# IEEE_EXT_Base_Centr.net
KiCad netlist of a schematic drawn in EAGLE
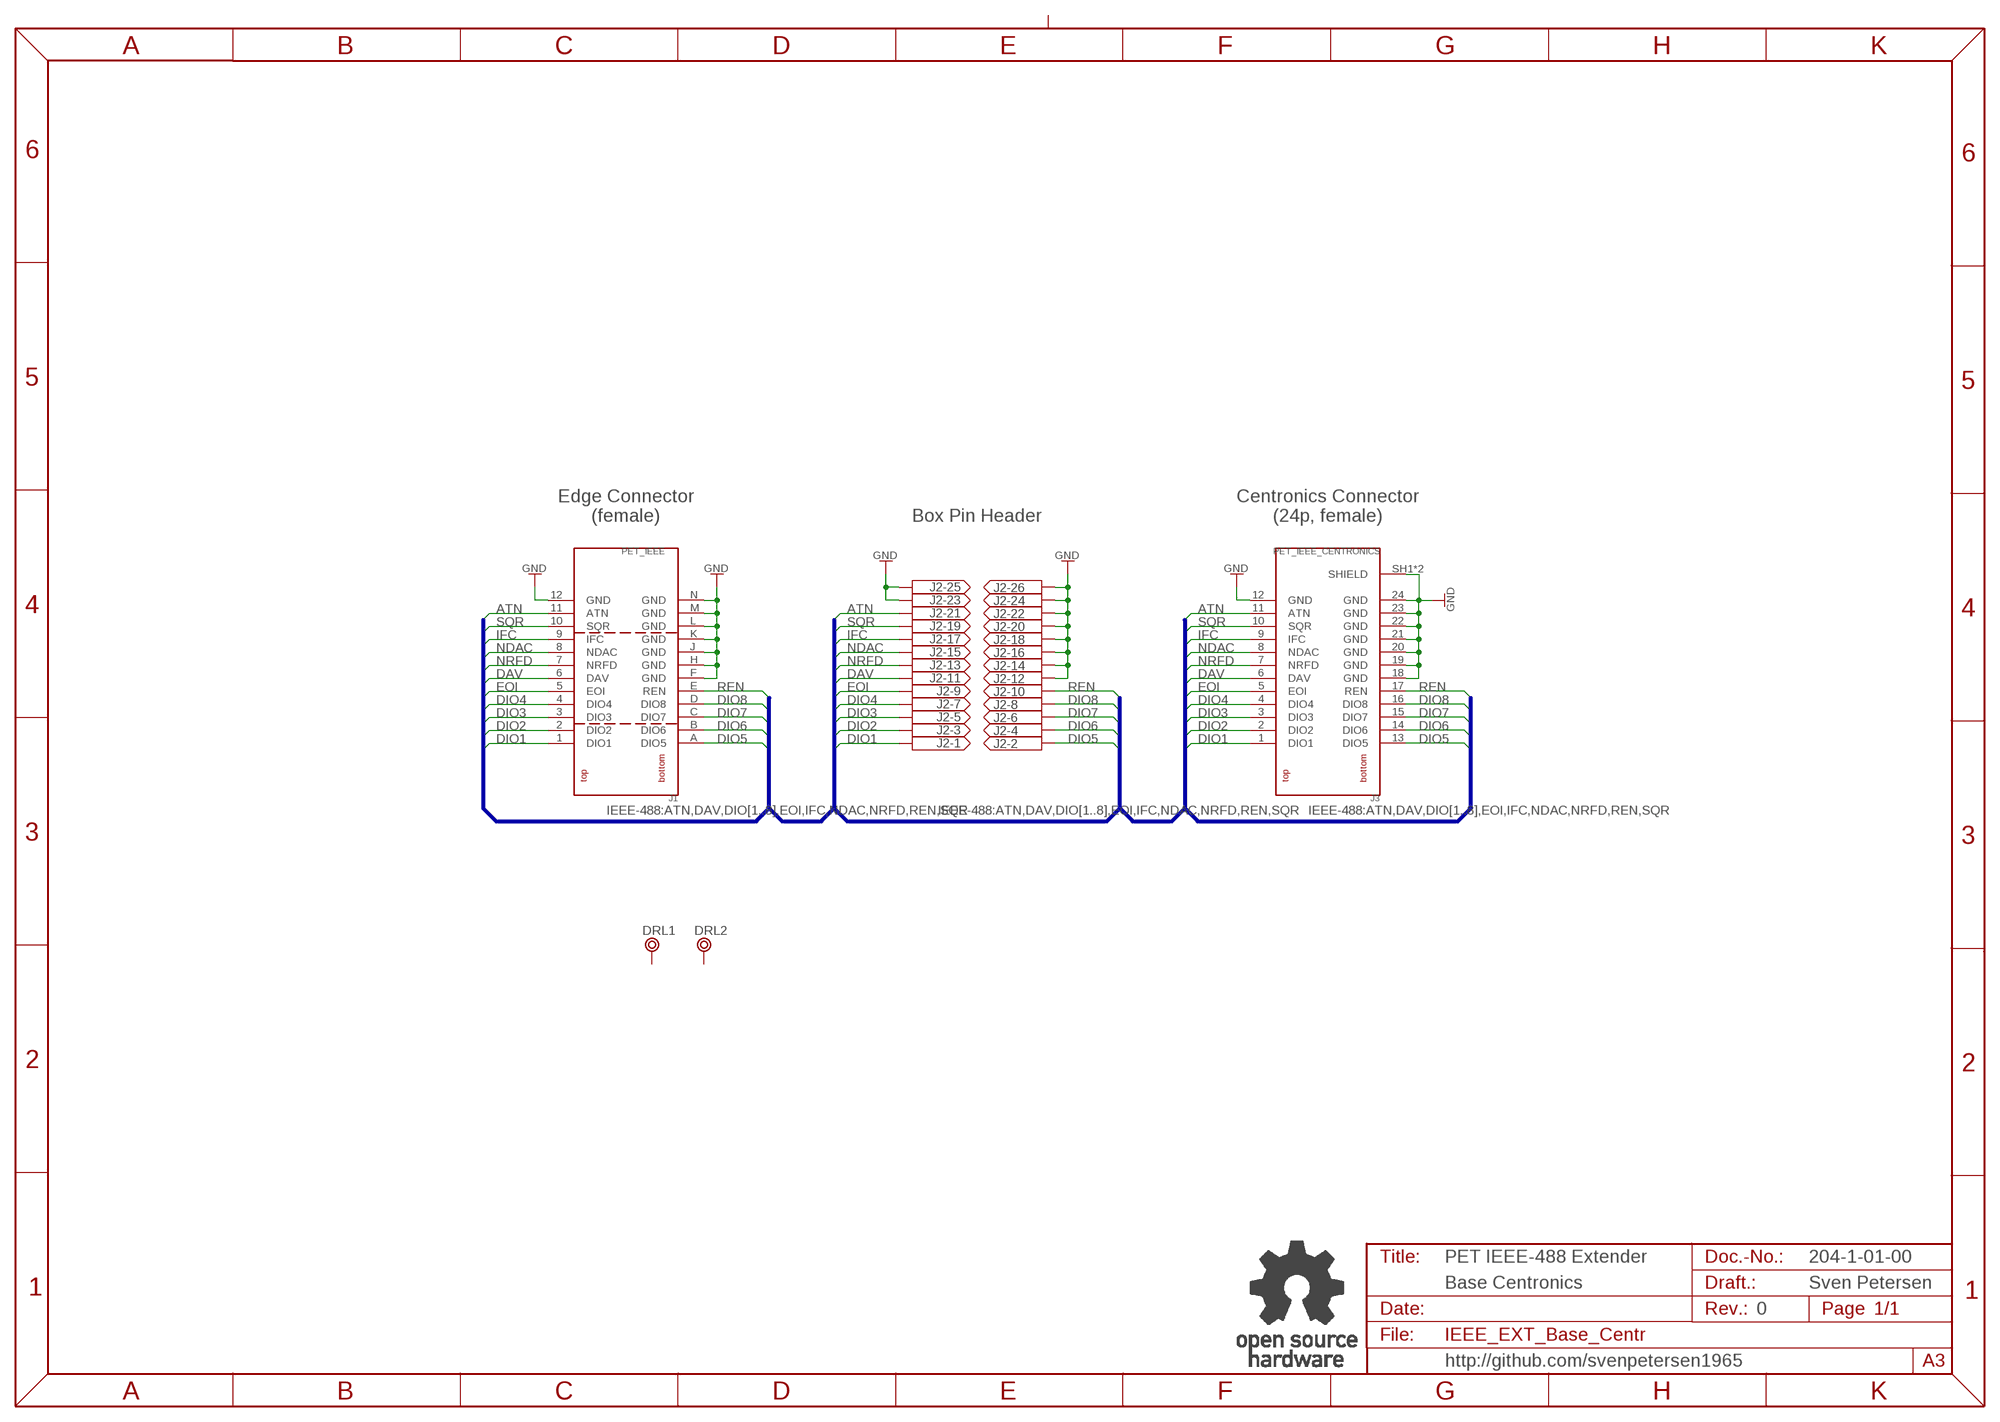
[diagram p0: schematic, sheet 1]

(export (version "E")
  (design (tool "Eeschema 10.0.6"))
  (components
    (comp (ref "DRL1")
      (value "BOHR3,5")
      (footprint "eagle-import:BOHR3,5")
      (libsource (lib "eagle-import") (part "BOHR3,5"))
    )
    (comp (ref "DRL2")
      (value "BOHR3,5")
      (footprint "eagle-import:BOHR3,5")
      (libsource (lib "eagle-import") (part "BOHR3,5"))
    )
    (comp (ref "J1")
      (value "PET_IEEE")
      (footprint "eagle-import:USERPORT")
      (libsource (lib "eagle-import") (part "PET_IEEE"))
    )
    (comp (ref "J2")
      (value "2X13WANNE")
      (footprint "eagle-import:2X13WV")
      (libsource (lib "eagle-import") (part "2X13WANNE"))
    )
    (comp (ref "J3")
      (value "PET_IEEE_CENTRONICS")
      (footprint "eagle-import:CENTRONICS24")
      (libsource (lib "eagle-import") (part "PET_IEEE_CENTRONICS"))
    )
    (comp (ref "U$9")
      (value "OPEN_SOURCE_HW")
      (footprint "eagle-import:OPENHW")
      (libsource (lib "eagle-import") (part "OPEN_SOURCE_HW"))
    )
  )
  (nets
    (net (code "2") (name "/ATN") (class "Default")
      (node (ref "J1") (pin "11") (pinfunction "ATN_11") (pintype "output"))
      (node (ref "J2") (pin "21") (pinfunction "1_21") (pintype "bidirectional"))
      (node (ref "J3") (pin "11") (pinfunction "ATN_11") (pintype "output"))
    )
    (net (code "3") (name "/DAV") (class "Default")
      (node (ref "J1") (pin "6") (pinfunction "DAV_6") (pintype "bidirectional"))
      (node (ref "J2") (pin "11") (pinfunction "1_11") (pintype "bidirectional"))
      (node (ref "J3") (pin "6") (pinfunction "DAV_6") (pintype "bidirectional"))
    )
    (net (code "4") (name "/DIO1") (class "Default")
      (node (ref "J1") (pin "1") (pinfunction "DIO1_1") (pintype "bidirectional"))
      (node (ref "J2") (pin "1") (pinfunction "1_1") (pintype "bidirectional"))
      (node (ref "J3") (pin "1") (pinfunction "DIO1_1") (pintype "bidirectional"))
    )
    (net (code "5") (name "/DIO2") (class "Default")
      (node (ref "J1") (pin "2") (pinfunction "DIO2_2") (pintype "bidirectional"))
      (node (ref "J2") (pin "3") (pinfunction "1_3") (pintype "bidirectional"))
      (node (ref "J3") (pin "2") (pinfunction "DIO2_2") (pintype "bidirectional"))
    )
    (net (code "6") (name "/DIO3") (class "Default")
      (node (ref "J1") (pin "3") (pinfunction "DIO3_3") (pintype "bidirectional"))
      (node (ref "J2") (pin "5") (pinfunction "1_5") (pintype "bidirectional"))
      (node (ref "J3") (pin "3") (pinfunction "DIO3_3") (pintype "bidirectional"))
    )
    (net (code "7") (name "/DIO4") (class "Default")
      (node (ref "J1") (pin "4") (pinfunction "DIO4_4") (pintype "bidirectional"))
      (node (ref "J2") (pin "7") (pinfunction "1_7") (pintype "bidirectional"))
      (node (ref "J3") (pin "4") (pinfunction "DIO4_4") (pintype "bidirectional"))
    )
    (net (code "8") (name "/DIO5") (class "Default")
      (node (ref "J1") (pin "A") (pinfunction "DIO5_A") (pintype "bidirectional"))
      (node (ref "J2") (pin "2") (pinfunction "1_2") (pintype "bidirectional"))
      (node (ref "J3") (pin "13") (pinfunction "DIO5_13") (pintype "bidirectional"))
    )
    (net (code "9") (name "/DIO6") (class "Default")
      (node (ref "J1") (pin "B") (pinfunction "DIO6_B") (pintype "bidirectional"))
      (node (ref "J2") (pin "4") (pinfunction "1_4") (pintype "bidirectional"))
      (node (ref "J3") (pin "14") (pinfunction "DIO6_14") (pintype "bidirectional"))
    )
    (net (code "10") (name "/DIO7") (class "Default")
      (node (ref "J1") (pin "C") (pinfunction "DIO7_C") (pintype "bidirectional"))
      (node (ref "J2") (pin "6") (pinfunction "1_6") (pintype "bidirectional"))
      (node (ref "J3") (pin "15") (pinfunction "DIO7_15") (pintype "bidirectional"))
    )
    (net (code "11") (name "/DIO8") (class "Default")
      (node (ref "J1") (pin "D") (pinfunction "DIO8_D") (pintype "bidirectional"))
      (node (ref "J2") (pin "8") (pinfunction "1_8") (pintype "bidirectional"))
      (node (ref "J3") (pin "16") (pinfunction "DIO8_16") (pintype "bidirectional"))
    )
    (net (code "12") (name "/EOI") (class "Default")
      (node (ref "J1") (pin "5") (pinfunction "EOI_5") (pintype "input"))
      (node (ref "J2") (pin "9") (pinfunction "1_9") (pintype "bidirectional"))
      (node (ref "J3") (pin "5") (pinfunction "EOI_5") (pintype "input"))
    )
    (net (code "13") (name "/IFC") (class "Default")
      (node (ref "J1") (pin "9") (pinfunction "IFC_9") (pintype "bidirectional"))
      (node (ref "J2") (pin "17") (pinfunction "1_17") (pintype "bidirectional"))
      (node (ref "J3") (pin "9") (pinfunction "IFC_9") (pintype "bidirectional"))
    )
    (net (code "14") (name "/NDAC") (class "Default")
      (node (ref "J1") (pin "8") (pinfunction "NDAC_8") (pintype "bidirectional"))
      (node (ref "J2") (pin "15") (pinfunction "1_15") (pintype "bidirectional"))
      (node (ref "J3") (pin "8") (pinfunction "NDAC_8") (pintype "bidirectional"))
    )
    (net (code "15") (name "/NRFD") (class "Default")
      (node (ref "J1") (pin "7") (pinfunction "NRFD_7") (pintype "bidirectional"))
      (node (ref "J2") (pin "13") (pinfunction "1_13") (pintype "bidirectional"))
      (node (ref "J3") (pin "7") (pinfunction "NRFD_7") (pintype "bidirectional"))
    )
    (net (code "16") (name "/REN") (class "Default")
      (node (ref "J1") (pin "E") (pinfunction "REN_E") (pintype "bidirectional"))
      (node (ref "J2") (pin "10") (pinfunction "1_10") (pintype "bidirectional"))
      (node (ref "J3") (pin "17") (pinfunction "REN_17") (pintype "bidirectional"))
    )
    (net (code "17") (name "/SQR") (class "Default")
      (node (ref "J1") (pin "10") (pinfunction "SQR_10") (pintype "bidirectional"))
      (node (ref "J2") (pin "19") (pinfunction "1_19") (pintype "bidirectional"))
      (node (ref "J3") (pin "10") (pinfunction "SQR_10") (pintype "bidirectional"))
    )
    (net (code "19") (name "GND") (class "Default")
      (node (ref "J1") (pin "12") (pinfunction "GND_12") (pintype "power_in"))
      (node (ref "J1") (pin "F") (pinfunction "GND_F") (pintype "power_in"))
      (node (ref "J1") (pin "H") (pinfunction "GND_H") (pintype "power_in"))
      (node (ref "J1") (pin "J") (pinfunction "GND_J") (pintype "power_in"))
      (node (ref "J1") (pin "K") (pinfunction "GND_K") (pintype "power_in"))
      (node (ref "J1") (pin "L") (pinfunction "GND_L") (pintype "power_in"))
      (node (ref "J1") (pin "M") (pinfunction "GND_M") (pintype "power_in"))
      (node (ref "J1") (pin "N") (pinfunction "GND_N") (pintype "power_in"))
      (node (ref "J2") (pin "12") (pinfunction "1_12") (pintype "bidirectional"))
      (node (ref "J2") (pin "14") (pinfunction "1_14") (pintype "bidirectional"))
      (node (ref "J2") (pin "16") (pinfunction "1_16") (pintype "bidirectional"))
      (node (ref "J2") (pin "18") (pinfunction "1_18") (pintype "bidirectional"))
      (node (ref "J2") (pin "20") (pinfunction "1_20") (pintype "bidirectional"))
      (node (ref "J2") (pin "22") (pinfunction "1_22") (pintype "bidirectional"))
      (node (ref "J2") (pin "23") (pinfunction "1_23") (pintype "bidirectional"))
      (node (ref "J2") (pin "24") (pinfunction "1_24") (pintype "bidirectional"))
      (node (ref "J2") (pin "25") (pinfunction "1_25") (pintype "bidirectional"))
      (node (ref "J2") (pin "26") (pinfunction "1_26") (pintype "bidirectional"))
      (node (ref "J3") (pin "12") (pinfunction "GND_12") (pintype "power_in"))
      (node (ref "J3") (pin "18") (pinfunction "GND_18") (pintype "power_in"))
      (node (ref "J3") (pin "19") (pinfunction "GND_19") (pintype "power_in"))
      (node (ref "J3") (pin "20") (pinfunction "GND_20") (pintype "power_in"))
      (node (ref "J3") (pin "21") (pinfunction "GND_21") (pintype "power_in"))
      (node (ref "J3") (pin "22") (pinfunction "GND_22") (pintype "power_in"))
      (node (ref "J3") (pin "23") (pinfunction "GND_23") (pintype "power_in"))
      (node (ref "J3") (pin "24") (pinfunction "GND_24") (pintype "power_in"))
      (node (ref "J3") (pin "SH1") (pinfunction "SHIELD_SH1") (pintype "bidirectional"))
      (node (ref "J3") (pin "SH2") (pinfunction "SHIELD_SH2") (pintype "bidirectional"))
    )
    (net (code "20") (name "unconnected-(DRL1-PadP$1)") (class "Default")
      (node (ref "DRL1") (pin "P$1") (pinfunction "P$1_P$1") (pintype "passive"))
    )
    (net (code "21") (name "unconnected-(DRL2-PadP$1)") (class "Default")
      (node (ref "DRL2") (pin "P$1") (pinfunction "P$1_P$1") (pintype "passive"))
    )
  )
)
